# ATtiny167_Study.net
KiCad netlist of a schematic drawn in EAGLE
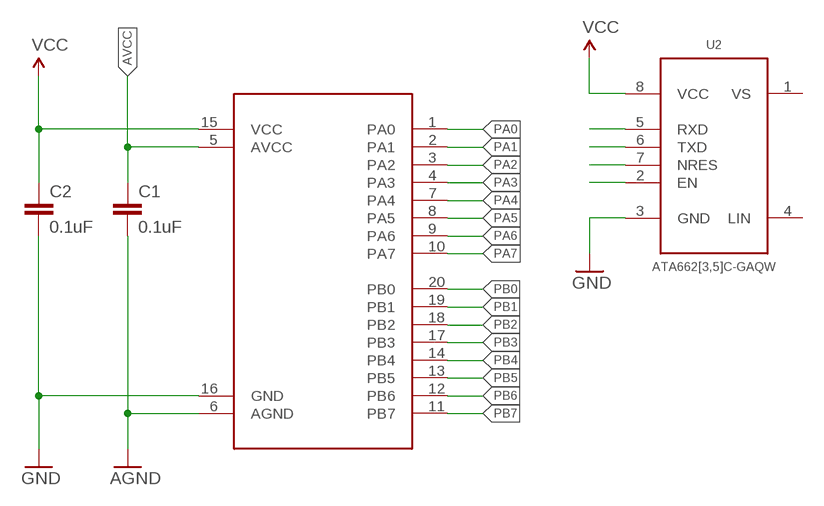
[diagram p0: schematic, sheet 1]

(export (version "E")
  (design (tool "Eeschema 10.0.6"))
  (components
    (comp (ref "C1")
      (value "0.1uF")
      (footprint "eagle-import:0603-CAP")
      (libsource (lib "eagle-import") (part "0.1UF-25V(+80/-20%)(0603)"))
    )
    (comp (ref "C2")
      (value "0.1uF")
      (footprint "eagle-import:0603-CAP")
      (libsource (lib "eagle-import") (part "0.1UF-25V(+80/-20%)(0603)"))
    )
    (comp (ref "U1")
      (value "ATTINY87-SU")
      (footprint "eagle-import:20S2")
      (libsource (lib "eagle-import") (part "ATTINY87SU-"))
    )
    (comp (ref "U2")
      (value "ATA662[3,5]C-GAQW")
      (footprint "eagle-import:8S1")
      (libsource (lib "eagle-import") (part "ATA662[3,5]CGAQW-"))
    )
  )
  (nets
    (net (code "1") (name "/VS") (class "Default")
      (node (ref "U2") (pin "1") (pinfunction "VS_1") (pintype "power_in"))
    )
    (net (code "2") (name "AGND") (class "Default")
      (node (ref "C1") (pin "2") (pinfunction "2_2") (pintype "passive"))
      (node (ref "U1") (pin "6") (pinfunction "AGND_6") (pintype "passive"))
    )
    (net (code "3") (name "AVCC") (class "Default")
      (node (ref "C1") (pin "1") (pinfunction "1_1") (pintype "passive"))
      (node (ref "U1") (pin "5") (pinfunction "AVCC_5") (pintype "power_in"))
    )
    (net (code "4") (name "GND") (class "Default")
      (node (ref "C2") (pin "2") (pinfunction "2_2") (pintype "passive"))
      (node (ref "U1") (pin "16") (pinfunction "GND_16") (pintype "passive"))
      (node (ref "U2") (pin "3") (pinfunction "GND_3") (pintype "passive"))
    )
    (net (code "5") (name "PA0") (class "Default")
      (node (ref "U1") (pin "1") (pinfunction "PA0_1") (pintype "bidirectional"))
    )
    (net (code "6") (name "PA1") (class "Default")
      (node (ref "U1") (pin "2") (pinfunction "PA1_2") (pintype "bidirectional"))
    )
    (net (code "7") (name "PA2") (class "Default")
      (node (ref "U1") (pin "3") (pinfunction "PA2_3") (pintype "bidirectional"))
    )
    (net (code "8") (name "PA3") (class "Default")
      (node (ref "U1") (pin "4") (pinfunction "PA3_4") (pintype "bidirectional"))
    )
    (net (code "9") (name "PA4") (class "Default")
      (node (ref "U1") (pin "7") (pinfunction "PA4_7") (pintype "bidirectional"))
    )
    (net (code "10") (name "PA5") (class "Default")
      (node (ref "U1") (pin "8") (pinfunction "PA5_8") (pintype "bidirectional"))
    )
    (net (code "11") (name "PA6") (class "Default")
      (node (ref "U1") (pin "9") (pinfunction "PA6_9") (pintype "bidirectional"))
    )
    (net (code "12") (name "PA7") (class "Default")
      (node (ref "U1") (pin "10") (pinfunction "PA7_10") (pintype "bidirectional"))
    )
    (net (code "13") (name "PB0") (class "Default")
      (node (ref "U1") (pin "20") (pinfunction "PB0_20") (pintype "bidirectional"))
    )
    (net (code "14") (name "PB1") (class "Default")
      (node (ref "U1") (pin "19") (pinfunction "PB1_19") (pintype "bidirectional"))
    )
    (net (code "15") (name "PB2") (class "Default")
      (node (ref "U1") (pin "18") (pinfunction "PB2_18") (pintype "bidirectional"))
    )
    (net (code "16") (name "PB3") (class "Default")
      (node (ref "U1") (pin "17") (pinfunction "PB3_17") (pintype "bidirectional"))
    )
    (net (code "17") (name "PB4") (class "Default")
      (node (ref "U1") (pin "14") (pinfunction "PB4_14") (pintype "bidirectional"))
    )
    (net (code "18") (name "PB5") (class "Default")
      (node (ref "U1") (pin "13") (pinfunction "PB5_13") (pintype "bidirectional"))
    )
    (net (code "19") (name "PB6") (class "Default")
      (node (ref "U1") (pin "12") (pinfunction "PB6_12") (pintype "bidirectional"))
    )
    (net (code "20") (name "PB7") (class "Default")
      (node (ref "U1") (pin "11") (pinfunction "PB7_11") (pintype "bidirectional"))
    )
    (net (code "21") (name "VCC") (class "Default")
      (node (ref "C2") (pin "1") (pinfunction "1_1") (pintype "passive"))
      (node (ref "U1") (pin "15") (pinfunction "VCC_15") (pintype "power_in"))
      (node (ref "U2") (pin "8") (pinfunction "VCC_8") (pintype "power_in"))
    )
    (net (code "22") (name "unconnected-(U2-EN-Pad2)") (class "Default")
      (node (ref "U2") (pin "2") (pinfunction "EN_2") (pintype "input"))
    )
    (net (code "23") (name "unconnected-(U2-LIN-Pad4)") (class "Default")
      (node (ref "U2") (pin "4") (pinfunction "LIN_4") (pintype "bidirectional"))
    )
    (net (code "24") (name "unconnected-(U2-NRES-Pad7)") (class "Default")
      (node (ref "U2") (pin "7") (pinfunction "NRES_7") (pintype "output"))
    )
    (net (code "25") (name "unconnected-(U2-RXD-Pad5)") (class "Default")
      (node (ref "U2") (pin "5") (pinfunction "RXD_5") (pintype "output"))
    )
    (net (code "26") (name "unconnected-(U2-TXD-Pad6)") (class "Default")
      (node (ref "U2") (pin "6") (pinfunction "TXD_6") (pintype "input"))
    )
  )
)
